# ife19_Elec_TS_accelpedal.net
KiCad netlist of a schematic drawn in Altium Designer
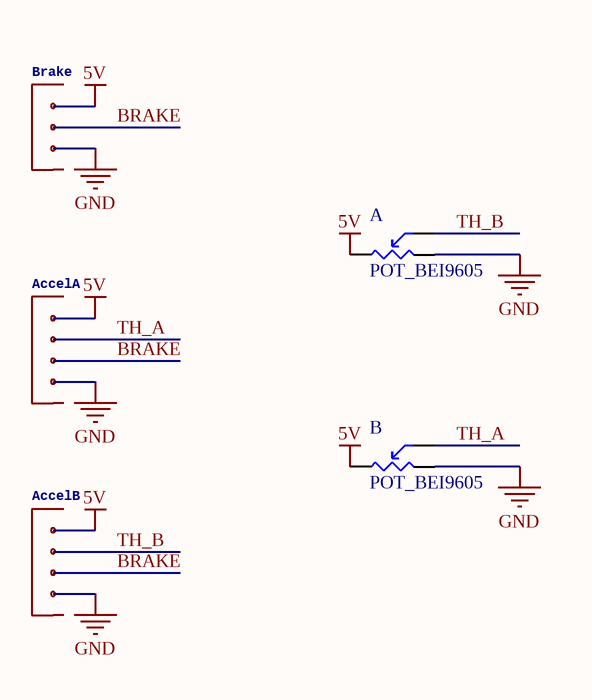
[diagram p0: ife19_Elec_TS_accelpedal.SchDoc]

(export (version "E")
  (design (tool "Eeschema 10.0.6"))
  (components
    (comp (ref "A")
      (value "POT_BEI9605")
      (footprint "POT_BEI9605")
      (libsource (lib "altium-import") (part "root_0_POT_BEI9605_"))
    )
    (comp (ref "AccelA")
      (value "Molex 505575-04 4 Position 2.00mm pitch connector wire to board connector Datasheet")
      (footprint "505578-04")
      (fields (field (name "LIBRARYNAME") "MOLEX Micro-Lock"))
      (libsource (lib "altium-import") (part "root_0_POS4_ML505578-04_"))
    )
    (comp (ref "AccelB")
      (value "Molex 505575-04 4 Position 2.00mm pitch connector wire to board connector Datasheet")
      (footprint "505578-04")
      (fields (field (name "LIBRARYNAME") "MOLEX Micro-Lock"))
      (libsource (lib "altium-import") (part "root_0_POS4_ML505578-04_"))
    )
    (comp (ref "B")
      (value "POT_BEI9605")
      (footprint "POT_BEI9605")
      (libsource (lib "altium-import") (part "root_0_POT_BEI9605_"))
    )
    (comp (ref "Brake")
      (value "Molex 505575-03 3 Position 2.00mm pitch connector wire to board connector Datasheet")
      (footprint "505578-03")
      (fields (field (name "LIBRARYNAME") "MOLEX Micro-Lock"))
      (libsource (lib "altium-import") (part "root_0_POS3_ML505578-03_"))
    )
  )
  (nets
    (net (code "1") (name "/BRAKE") (class "Default")
      (node (ref "AccelA") (pin "3") (pinfunction "3_3") (pintype "passive"))
      (node (ref "AccelB") (pin "3") (pinfunction "3_3") (pintype "passive"))
      (node (ref "Brake") (pin "2") (pinfunction "2_2") (pintype "passive"))
    )
    (net (code "2") (name "/TH_A") (class "Default")
      (node (ref "AccelA") (pin "2") (pinfunction "2_2") (pintype "passive"))
      (node (ref "B") (pin "2") (pinfunction "2_2") (pintype "passive"))
    )
    (net (code "3") (name "/TH_B") (class "Default")
      (node (ref "A") (pin "2") (pinfunction "2_2") (pintype "passive"))
      (node (ref "AccelB") (pin "2") (pinfunction "2_2") (pintype "passive"))
    )
    (net (code "4") (name "5V") (class "Default")
      (node (ref "A") (pin "3") (pinfunction "3_3") (pintype "passive"))
      (node (ref "AccelA") (pin "1") (pinfunction "1_1") (pintype "passive"))
      (node (ref "AccelB") (pin "1") (pinfunction "1_1") (pintype "passive"))
      (node (ref "B") (pin "3") (pinfunction "3_3") (pintype "passive"))
      (node (ref "Brake") (pin "1") (pinfunction "1_1") (pintype "passive"))
    )
    (net (code "5") (name "GND") (class "Default")
      (node (ref "A") (pin "1") (pinfunction "1_1") (pintype "passive"))
      (node (ref "AccelA") (pin "4") (pinfunction "4_4") (pintype "passive"))
      (node (ref "AccelB") (pin "4") (pinfunction "4_4") (pintype "passive"))
      (node (ref "B") (pin "1") (pinfunction "1_1") (pintype "passive"))
      (node (ref "Brake") (pin "3") (pinfunction "3_3") (pintype "passive"))
    )
  )
)
